# Sheet1.net
KiCad netlist of a schematic drawn in Altium Designer
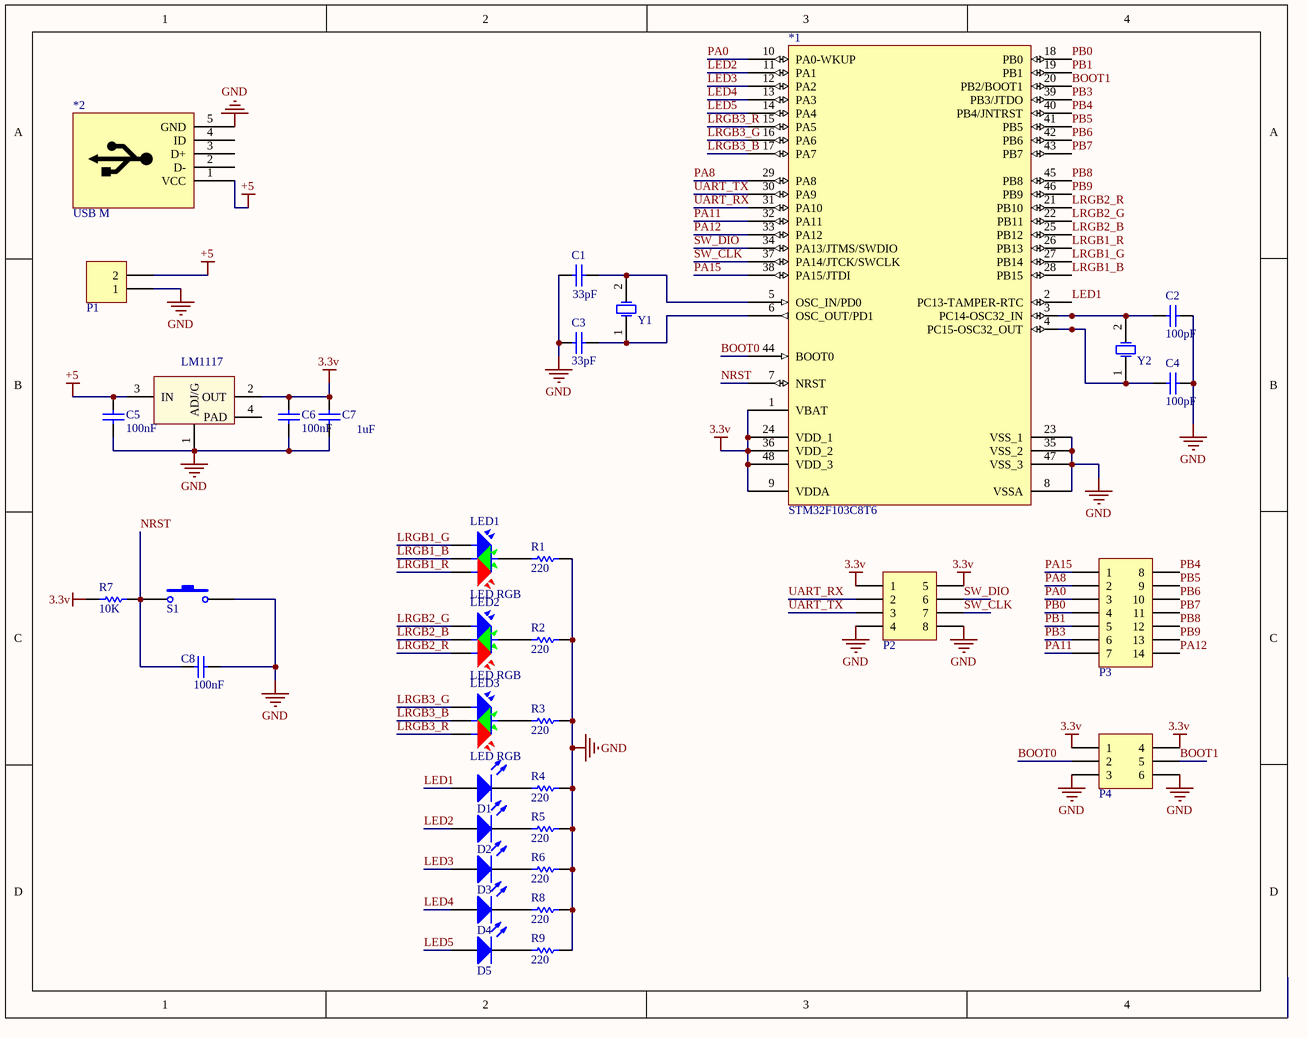
[diagram p0: Sheet1.SchDoc]

(export (version "E")
  (design (tool "Eeschema 10.0.6"))
  (components
    (comp (ref "*1")
      (value "STM32F103C8T6")
      (footprint "TSQFP50P900X900X160-48N")
      (fields (field (name "MANUFACTURER") "ST"))
      (libsource (lib "MiclsLib") (part "STM32F103C8T6"))
    )
    (comp (ref "*2")
      (value "USB M")
      (footprint "USB-B-MINI-SMD")
      (libsource (lib "My library altium") (part "USB M"))
    )
    (comp (ref "C1")
      (value "33pF")
      (footprint "CAP-SM-0805")
      (description "Capacitor")
      (fields (field (name "Comment") "Cap Non-Pol SMD"))
      (libsource (lib "PIF_Library") (part "Cap Non-Pol SMD"))
    )
    (comp (ref "C2")
      (value "100pF")
      (footprint "CAP-SM-0805")
      (description "Capacitor")
      (fields (field (name "Comment") "Cap Non-Pol SMD"))
      (libsource (lib "PIF_Library") (part "Cap Non-Pol SMD"))
    )
    (comp (ref "C3")
      (value "33pF")
      (footprint "CAP-SM-0805")
      (description "Capacitor")
      (fields (field (name "Comment") "Cap Non-Pol SMD"))
      (libsource (lib "PIF_Library") (part "Cap Non-Pol SMD"))
    )
    (comp (ref "C4")
      (value "100pF")
      (footprint "CAP-SM-0805")
      (description "Capacitor")
      (fields (field (name "Comment") "Cap Non-Pol SMD"))
      (libsource (lib "PIF_Library") (part "Cap Non-Pol SMD"))
    )
    (comp (ref "C5")
      (value "100nF")
      (footprint "CAP-SM-0805")
      (description "Capacitor")
      (fields (field (name "Comment") "Cap Non-Pol SMD"))
      (libsource (lib "PIF_Library") (part "Cap Non-Pol SMD"))
    )
    (comp (ref "C6")
      (value "100nF")
      (footprint "CAP-SM-0805")
      (description "Capacitor")
      (fields (field (name "Comment") "Cap Non-Pol SMD"))
      (libsource (lib "PIF_Library") (part "Cap Non-Pol SMD"))
    )
    (comp (ref "C7")
      (value "1uF")
      (footprint "CAP-SM-0805")
      (description "Capacitor")
      (fields (field (name "Comment") "Cap Non-Pol SMD"))
      (libsource (lib "PIF_Library") (part "Cap Non-Pol SMD"))
    )
    (comp (ref "C8")
      (value "100nF")
      (footprint "CAP-SM-0805")
      (description "Capacitor")
      (fields (field (name "Comment") "Cap Non-Pol SMD"))
      (libsource (lib "PIF_Library") (part "Cap Non-Pol SMD"))
    )
    (comp (ref "D1")
      (value "LED SMD")
      (footprint "LED_0603_Blue")
      (description "LED")
      (libsource (lib "PIF_Library") (part "LED SMD"))
    )
    (comp (ref "D2")
      (value "LED SMD")
      (footprint "LED_0603_Blue")
      (description "LED")
      (libsource (lib "PIF_Library") (part "LED SMD"))
    )
    (comp (ref "D3")
      (value "LED SMD")
      (footprint "LED_0603_Blue")
      (description "LED")
      (libsource (lib "PIF_Library") (part "LED SMD"))
    )
    (comp (ref "D4")
      (value "LED SMD")
      (footprint "LED_0603_Blue")
      (description "LED")
      (libsource (lib "PIF_Library") (part "LED SMD"))
    )
    (comp (ref "D5")
      (value "LED SMD")
      (footprint "LED_0603_Blue")
      (description "LED")
      (libsource (lib "PIF_Library") (part "LED SMD"))
    )
    (comp (ref "LED1")
      (value "LED RGB")
      (footprint "led rgb")
      (libsource (lib "My library altium") (part "LED RGB"))
    )
    (comp (ref "LED2")
      (value "LED RGB")
      (footprint "led rgb")
      (libsource (lib "My library altium") (part "LED RGB"))
    )
    (comp (ref "LED3")
      (value "LED RGB")
      (footprint "led rgb")
      (libsource (lib "My library altium") (part "LED RGB"))
    )
    (comp (ref "LM1117")
      (value "LM1117")
      (footprint "SOT223-4N")
      (description "Available in 1.8V, 2.5V, 2.85V, 3.3V, 5V, and  Adjustable Versions")
      (libsource (lib "PIF_Library") (part "LM1117"))
    )
    (comp (ref "P1")
      (value "Domino 2")
      (footprint "DOMINO 2- 5mm")
      (description "Domino, 2-Pin")
      (fields (field (name "PUBLISHER") "Altium Limited"))
      (libsource (lib "PIF_Library") (part "Domino 2"))
    )
    (comp (ref "P2")
      (value "Header 4X2")
      (footprint "JP4x2")
      (description "Header, 4-Pin, Dual row")
      (fields (field (name "PUBLISHER") "Altium Limited"))
      (libsource (lib "PIF_Library") (part "Header 4X2"))
    )
    (comp (ref "P3")
      (value "Header 7X2")
      (footprint "JP7X2")
      (description "Header, 7-Pin, Dual row")
      (fields (field (name "PUBLISHER") "Altium Limited"))
      (libsource (lib "PIF_Library") (part "Header 7X2"))
    )
    (comp (ref "P4")
      (value "Header 3X2")
      (footprint "JP3x2")
      (description "Header, 3-Pin, Dual row")
      (fields (field (name "PUBLISHER") "Altium Limited"))
      (libsource (lib "PIF_Library") (part "Header 3X2"))
    )
    (comp (ref "R1")
      (value "220")
      (footprint "RES-SM-0603")
      (description "Resistor")
      (fields (field (name "Comment") "RESISTOR SMD"))
      (libsource (lib "PIF_Library") (part "RESISTOR SMD"))
    )
    (comp (ref "R2")
      (value "220")
      (footprint "RES-SM-0603")
      (description "Resistor")
      (fields (field (name "Comment") "RESISTOR SMD"))
      (libsource (lib "PIF_Library") (part "RESISTOR SMD"))
    )
    (comp (ref "R3")
      (value "220")
      (footprint "RES-SM-0603")
      (description "Resistor")
      (fields (field (name "Comment") "RESISTOR SMD"))
      (libsource (lib "PIF_Library") (part "RESISTOR SMD"))
    )
    (comp (ref "R4")
      (value "220")
      (footprint "RES-SM-0603")
      (description "Resistor")
      (fields (field (name "Comment") "RESISTOR SMD"))
      (libsource (lib "PIF_Library") (part "RESISTOR SMD"))
    )
    (comp (ref "R5")
      (value "220")
      (footprint "RES-SM-0603")
      (description "Resistor")
      (fields (field (name "Comment") "RESISTOR SMD"))
      (libsource (lib "PIF_Library") (part "RESISTOR SMD"))
    )
    (comp (ref "R6")
      (value "220")
      (footprint "RES-SM-0603")
      (description "Resistor")
      (fields (field (name "Comment") "RESISTOR SMD"))
      (libsource (lib "PIF_Library") (part "RESISTOR SMD"))
    )
    (comp (ref "R7")
      (value "10K")
      (footprint "RES-SM-0603")
      (description "Resistor")
      (fields (field (name "Comment") "RESISTOR SMD"))
      (libsource (lib "PIF_Library") (part "RESISTOR SMD"))
    )
    (comp (ref "R8")
      (value "220")
      (footprint "RES-SM-0603")
      (description "Resistor")
      (fields (field (name "Comment") "RESISTOR SMD"))
      (libsource (lib "PIF_Library") (part "RESISTOR SMD"))
    )
    (comp (ref "R9")
      (value "220")
      (footprint "RES-SM-0603")
      (description "Resistor")
      (fields (field (name "Comment") "RESISTOR SMD"))
      (libsource (lib "PIF_Library") (part "RESISTOR SMD"))
    )
    (comp (ref "S1")
      (value "Tact SW - 2Pin")
      (footprint "SW2")
      (description "Switch button 2 pin")
      (libsource (lib "PIF_Library") (part "Tact SW - 2Pin"))
    )
    (comp (ref "Y1")
      (value "XTAL")
      (footprint "XTAL 32KN")
      (description "Crystal Oscillator")
      (fields (field (name "PUBLISHER") "Altium Limited"))
      (libsource (lib "PIF_Library") (part "XTAL"))
    )
    (comp (ref "Y2")
      (value "XTAL")
      (footprint "XTAL 32KN")
      (description "Crystal Oscillator")
      (fields (field (name "PUBLISHER") "Altium Limited"))
      (libsource (lib "PIF_Library") (part "XTAL"))
    )
  )
  (nets
    (net (code "1") (name "+5") (class "Default")
      (node (ref "*2") (pin "1") (pinfunction "VCC_1") (pintype "passive"))
      (node (ref "C5") (pin "1") (pinfunction "1_1") (pintype "passive"))
      (node (ref "LM1117") (pin "3") (pinfunction "IN_3") (pintype "passive"))
      (node (ref "P1") (pin "2") (pinfunction "2_2") (pintype "passive"))
    )
    (net (code "2") (name "/BOOT0") (class "Default")
      (node (ref "*1") (pin "44") (pinfunction "BOOT0_44") (pintype "input"))
      (node (ref "P4") (pin "2") (pinfunction "2_2") (pintype "passive"))
    )
    (net (code "3") (name "/BOOT1") (class "Default")
      (node (ref "*1") (pin "20") (pinfunction "PB2/BOOT1_20") (pintype "bidirectional"))
      (node (ref "P4") (pin "5") (pinfunction "5_5") (pintype "passive"))
    )
    (net (code "4") (name "/LED1") (class "Default")
      (node (ref "*1") (pin "2") (pinfunction "PC13-TAMPER-RTC_2") (pintype "bidirectional"))
      (node (ref "D1") (pin "1") (pinfunction "A_1") (pintype "passive"))
    )
    (net (code "5") (name "/LED2") (class "Default")
      (node (ref "*1") (pin "11") (pinfunction "PA1_11") (pintype "bidirectional"))
      (node (ref "D2") (pin "1") (pinfunction "A_1") (pintype "passive"))
    )
    (net (code "6") (name "/LED3") (class "Default")
      (node (ref "*1") (pin "12") (pinfunction "PA2_12") (pintype "bidirectional"))
      (node (ref "D3") (pin "1") (pinfunction "A_1") (pintype "passive"))
    )
    (net (code "7") (name "/LED4") (class "Default")
      (node (ref "*1") (pin "13") (pinfunction "PA3_13") (pintype "bidirectional"))
      (node (ref "D4") (pin "1") (pinfunction "A_1") (pintype "passive"))
    )
    (net (code "8") (name "/LED5") (class "Default")
      (node (ref "*1") (pin "14") (pinfunction "PA4_14") (pintype "bidirectional"))
      (node (ref "D5") (pin "1") (pinfunction "A_1") (pintype "passive"))
    )
    (net (code "9") (name "/LRGB1_B") (class "Default")
      (node (ref "*1") (pin "28") (pinfunction "PB15_28") (pintype "bidirectional"))
      (node (ref "LED1") (pin "1") (pinfunction "1_1") (pintype "passive"))
    )
    (net (code "10") (name "/LRGB1_G") (class "Default")
      (node (ref "*1") (pin "27") (pinfunction "PB14_27") (pintype "bidirectional"))
      (node (ref "LED1") (pin "2") (pinfunction "2_2") (pintype "passive"))
    )
    (net (code "11") (name "/LRGB1_R") (class "Default")
      (node (ref "*1") (pin "26") (pinfunction "PB13_26") (pintype "bidirectional"))
      (node (ref "LED1") (pin "4") (pinfunction "4_4") (pintype "passive"))
    )
    (net (code "12") (name "/LRGB2_B") (class "Default")
      (node (ref "*1") (pin "25") (pinfunction "PB12_25") (pintype "bidirectional"))
      (node (ref "LED2") (pin "1") (pinfunction "1_1") (pintype "passive"))
    )
    (net (code "13") (name "/LRGB2_G") (class "Default")
      (node (ref "*1") (pin "22") (pinfunction "PB11_22") (pintype "bidirectional"))
      (node (ref "LED2") (pin "2") (pinfunction "2_2") (pintype "passive"))
    )
    (net (code "14") (name "/LRGB2_R") (class "Default")
      (node (ref "*1") (pin "21") (pinfunction "PB10_21") (pintype "bidirectional"))
      (node (ref "LED2") (pin "4") (pinfunction "4_4") (pintype "passive"))
    )
    (net (code "15") (name "/LRGB3_B") (class "Default")
      (node (ref "*1") (pin "17") (pinfunction "PA7_17") (pintype "bidirectional"))
      (node (ref "LED3") (pin "1") (pinfunction "1_1") (pintype "passive"))
    )
    (net (code "16") (name "/LRGB3_G") (class "Default")
      (node (ref "*1") (pin "16") (pinfunction "PA6_16") (pintype "bidirectional"))
      (node (ref "LED3") (pin "2") (pinfunction "2_2") (pintype "passive"))
    )
    (net (code "17") (name "/LRGB3_R") (class "Default")
      (node (ref "*1") (pin "15") (pinfunction "PA5_15") (pintype "bidirectional"))
      (node (ref "LED3") (pin "4") (pinfunction "4_4") (pintype "passive"))
    )
    (net (code "18") (name "/NRST") (class "Default")
      (node (ref "*1") (pin "7") (pinfunction "NRST_7") (pintype "bidirectional"))
      (node (ref "C8") (pin "1") (pinfunction "1_1") (pintype "passive"))
      (node (ref "R7") (pin "2") (pinfunction "2_2") (pintype "passive"))
      (node (ref "S1") (pin "1") (pinfunction "1_1") (pintype "passive"))
    )
    (net (code "19") (name "/PA0") (class "Default")
      (node (ref "*1") (pin "10") (pinfunction "PA0-WKUP_10") (pintype "bidirectional"))
      (node (ref "P3") (pin "3") (pinfunction "3_3") (pintype "passive"))
    )
    (net (code "20") (name "/PA8") (class "Default")
      (node (ref "*1") (pin "29") (pinfunction "PA8_29") (pintype "bidirectional"))
      (node (ref "P3") (pin "2") (pinfunction "2_2") (pintype "passive"))
    )
    (net (code "21") (name "/PA11") (class "Default")
      (node (ref "*1") (pin "32") (pinfunction "PA11_32") (pintype "bidirectional"))
      (node (ref "P3") (pin "7") (pinfunction "7_7") (pintype "passive"))
    )
    (net (code "22") (name "/PA12") (class "Default")
      (node (ref "*1") (pin "33") (pinfunction "PA12_33") (pintype "bidirectional"))
      (node (ref "P3") (pin "14") (pinfunction "14_14") (pintype "passive"))
    )
    (net (code "23") (name "/PA15") (class "Default")
      (node (ref "*1") (pin "38") (pinfunction "PA15/JTDI_38") (pintype "bidirectional"))
      (node (ref "P3") (pin "1") (pinfunction "1_1") (pintype "passive"))
    )
    (net (code "24") (name "/PB0") (class "Default")
      (node (ref "*1") (pin "18") (pinfunction "PB0_18") (pintype "bidirectional"))
      (node (ref "P3") (pin "4") (pinfunction "4_4") (pintype "passive"))
    )
    (net (code "25") (name "/PB1") (class "Default")
      (node (ref "*1") (pin "19") (pinfunction "PB1_19") (pintype "bidirectional"))
      (node (ref "P3") (pin "5") (pinfunction "5_5") (pintype "passive"))
    )
    (net (code "26") (name "/PB3") (class "Default")
      (node (ref "*1") (pin "39") (pinfunction "PB3/JTDO_39") (pintype "bidirectional"))
      (node (ref "P3") (pin "6") (pinfunction "6_6") (pintype "passive"))
    )
    (net (code "27") (name "/PB4") (class "Default")
      (node (ref "*1") (pin "40") (pinfunction "PB4/JNTRST_40") (pintype "bidirectional"))
      (node (ref "P3") (pin "8") (pinfunction "8_8") (pintype "passive"))
    )
    (net (code "28") (name "/PB5") (class "Default")
      (node (ref "*1") (pin "41") (pinfunction "PB5_41") (pintype "bidirectional"))
      (node (ref "P3") (pin "9") (pinfunction "9_9") (pintype "passive"))
    )
    (net (code "29") (name "/PB6") (class "Default")
      (node (ref "*1") (pin "42") (pinfunction "PB6_42") (pintype "bidirectional"))
      (node (ref "P3") (pin "10") (pinfunction "10_10") (pintype "passive"))
    )
    (net (code "30") (name "/PB7") (class "Default")
      (node (ref "*1") (pin "43") (pinfunction "PB7_43") (pintype "bidirectional"))
      (node (ref "P3") (pin "11") (pinfunction "11_11") (pintype "passive"))
    )
    (net (code "31") (name "/PB8") (class "Default")
      (node (ref "*1") (pin "45") (pinfunction "PB8_45") (pintype "bidirectional"))
      (node (ref "P3") (pin "12") (pinfunction "12_12") (pintype "passive"))
    )
    (net (code "32") (name "/PB9") (class "Default")
      (node (ref "*1") (pin "46") (pinfunction "PB9_46") (pintype "bidirectional"))
      (node (ref "P3") (pin "13") (pinfunction "13_13") (pintype "passive"))
    )
    (net (code "33") (name "/SW_CLK") (class "Default")
      (node (ref "*1") (pin "37") (pinfunction "PA14/JTCK/SWCLK_37") (pintype "bidirectional"))
      (node (ref "P2") (pin "7") (pinfunction "7_7") (pintype "passive"))
    )
    (net (code "34") (name "/SW_DIO") (class "Default")
      (node (ref "*1") (pin "34") (pinfunction "PA13/JTMS/SWDIO_34") (pintype "bidirectional"))
      (node (ref "P2") (pin "6") (pinfunction "6_6") (pintype "passive"))
    )
    (net (code "35") (name "/UART_RX") (class "Default")
      (node (ref "*1") (pin "31") (pinfunction "PA10_31") (pintype "bidirectional"))
      (node (ref "P2") (pin "2") (pinfunction "2_2") (pintype "passive"))
    )
    (net (code "36") (name "/UART_TX") (class "Default")
      (node (ref "*1") (pin "30") (pinfunction "PA9_30") (pintype "bidirectional"))
      (node (ref "P2") (pin "3") (pinfunction "3_3") (pintype "passive"))
    )
    (net (code "37") (name "3.3v") (class "Default")
      (node (ref "*1") (pin "1") (pinfunction "VBAT_1") (pintype "power_in"))
      (node (ref "*1") (pin "24") (pinfunction "VDD_1_24") (pintype "power_in"))
      (node (ref "*1") (pin "36") (pinfunction "VDD_2_36") (pintype "power_in"))
      (node (ref "*1") (pin "48") (pinfunction "VDD_3_48") (pintype "power_in"))
      (node (ref "*1") (pin "9") (pinfunction "VDDA_9") (pintype "power_in"))
      (node (ref "C6") (pin "1") (pinfunction "1_1") (pintype "passive"))
      (node (ref "C7") (pin "1") (pinfunction "1_1") (pintype "passive"))
      (node (ref "LM1117") (pin "2") (pinfunction "OUT_2") (pintype "passive"))
      (node (ref "P2") (pin "1") (pinfunction "1_1") (pintype "passive"))
      (node (ref "P2") (pin "5") (pinfunction "5_5") (pintype "passive"))
      (node (ref "P4") (pin "1") (pinfunction "1_1") (pintype "passive"))
      (node (ref "P4") (pin "4") (pinfunction "4_4") (pintype "passive"))
      (node (ref "R7") (pin "1") (pinfunction "1_1") (pintype "passive"))
    )
    (net (code "38") (name "GND") (class "Default")
      (node (ref "*1") (pin "23") (pinfunction "VSS_1_23") (pintype "power_in"))
      (node (ref "*1") (pin "35") (pinfunction "VSS_2_35") (pintype "power_in"))
      (node (ref "*1") (pin "47") (pinfunction "VSS_3_47") (pintype "power_in"))
      (node (ref "*1") (pin "8") (pinfunction "VSSA_8") (pintype "power_in"))
      (node (ref "*2") (pin "5") (pinfunction "GND_5") (pintype "passive"))
      (node (ref "C1") (pin "1") (pinfunction "1_1") (pintype "passive"))
      (node (ref "C2") (pin "2") (pinfunction "2_2") (pintype "passive"))
      (node (ref "C3") (pin "1") (pinfunction "1_1") (pintype "passive"))
      (node (ref "C4") (pin "2") (pinfunction "2_2") (pintype "passive"))
      (node (ref "C5") (pin "2") (pinfunction "2_2") (pintype "passive"))
      (node (ref "C6") (pin "2") (pinfunction "2_2") (pintype "passive"))
      (node (ref "C7") (pin "2") (pinfunction "2_2") (pintype "passive"))
      (node (ref "C8") (pin "2") (pinfunction "2_2") (pintype "passive"))
      (node (ref "LM1117") (pin "1") (pinfunction "ADJ/G_1") (pintype "passive"))
      (node (ref "P1") (pin "1") (pinfunction "1_1") (pintype "passive"))
      (node (ref "P2") (pin "4") (pinfunction "4_4") (pintype "passive"))
      (node (ref "P2") (pin "8") (pinfunction "8_8") (pintype "passive"))
      (node (ref "P4") (pin "3") (pinfunction "3_3") (pintype "passive"))
      (node (ref "P4") (pin "6") (pinfunction "6_6") (pintype "passive"))
      (node (ref "R1") (pin "1") (pinfunction "1_1") (pintype "passive"))
      (node (ref "R2") (pin "1") (pinfunction "1_1") (pintype "passive"))
      (node (ref "R3") (pin "1") (pinfunction "1_1") (pintype "passive"))
      (node (ref "R4") (pin "1") (pinfunction "1_1") (pintype "passive"))
      (node (ref "R5") (pin "1") (pinfunction "1_1") (pintype "passive"))
      (node (ref "R6") (pin "1") (pinfunction "1_1") (pintype "passive"))
      (node (ref "R8") (pin "1") (pinfunction "1_1") (pintype "passive"))
      (node (ref "R9") (pin "1") (pinfunction "1_1") (pintype "passive"))
      (node (ref "S1") (pin "2") (pinfunction "2_2") (pintype "passive"))
    )
    (net (code "39") (name "Net-(*1-OSC_IN{slash}PD0)") (class "Default")
      (node (ref "*1") (pin "5") (pinfunction "OSC_IN/PD0_5") (pintype "input"))
      (node (ref "C1") (pin "2") (pinfunction "2_2") (pintype "passive"))
      (node (ref "Y1") (pin "2") (pinfunction "OSC2_2") (pintype "passive"))
    )
    (net (code "40") (name "Net-(*1-OSC_OUT{slash}PD1)") (class "Default")
      (node (ref "*1") (pin "6") (pinfunction "OSC_OUT/PD1_6") (pintype "output"))
      (node (ref "C3") (pin "2") (pinfunction "2_2") (pintype "passive"))
      (node (ref "Y1") (pin "1") (pinfunction "OSC1_1") (pintype "passive"))
    )
    (net (code "41") (name "Net-(*1-PC14-OSC32_IN)") (class "Default")
      (node (ref "*1") (pin "3") (pinfunction "PC14-OSC32_IN_3") (pintype "bidirectional"))
      (node (ref "C2") (pin "1") (pinfunction "1_1") (pintype "passive"))
      (node (ref "Y2") (pin "2") (pinfunction "OSC2_2") (pintype "passive"))
    )
    (net (code "42") (name "Net-(*1-PC15-OSC32_OUT)") (class "Default")
      (node (ref "*1") (pin "4") (pinfunction "PC15-OSC32_OUT_4") (pintype "bidirectional"))
      (node (ref "C4") (pin "1") (pinfunction "1_1") (pintype "passive"))
      (node (ref "Y2") (pin "1") (pinfunction "OSC1_1") (pintype "passive"))
    )
    (net (code "43") (name "Net-(D1-K)") (class "Default")
      (node (ref "D1") (pin "2") (pinfunction "K_2") (pintype "passive"))
      (node (ref "R4") (pin "2") (pinfunction "2_2") (pintype "passive"))
    )
    (net (code "44") (name "Net-(D2-K)") (class "Default")
      (node (ref "D2") (pin "2") (pinfunction "K_2") (pintype "passive"))
      (node (ref "R5") (pin "2") (pinfunction "2_2") (pintype "passive"))
    )
    (net (code "45") (name "Net-(D3-K)") (class "Default")
      (node (ref "D3") (pin "2") (pinfunction "K_2") (pintype "passive"))
      (node (ref "R6") (pin "2") (pinfunction "2_2") (pintype "passive"))
    )
    (net (code "46") (name "Net-(D4-K)") (class "Default")
      (node (ref "D4") (pin "2") (pinfunction "K_2") (pintype "passive"))
      (node (ref "R8") (pin "2") (pinfunction "2_2") (pintype "passive"))
    )
    (net (code "47") (name "Net-(D5-K)") (class "Default")
      (node (ref "D5") (pin "2") (pinfunction "K_2") (pintype "passive"))
      (node (ref "R9") (pin "2") (pinfunction "2_2") (pintype "passive"))
    )
    (net (code "48") (name "Net-(LED1-Pad3)") (class "Default")
      (node (ref "LED1") (pin "3") (pinfunction "3_3") (pintype "passive"))
      (node (ref "R1") (pin "2") (pinfunction "2_2") (pintype "passive"))
    )
    (net (code "49") (name "Net-(LED2-Pad3)") (class "Default")
      (node (ref "LED2") (pin "3") (pinfunction "3_3") (pintype "passive"))
      (node (ref "R2") (pin "2") (pinfunction "2_2") (pintype "passive"))
    )
    (net (code "50") (name "Net-(LED3-Pad3)") (class "Default")
      (node (ref "LED3") (pin "3") (pinfunction "3_3") (pintype "passive"))
      (node (ref "R3") (pin "2") (pinfunction "2_2") (pintype "passive"))
    )
    (net (code "51") (name "unconnected-(*2-D+-Pad3)") (class "Default")
      (node (ref "*2") (pin "3") (pinfunction "D+_3") (pintype "passive"))
    )
    (net (code "52") (name "unconnected-(*2-D--Pad2)") (class "Default")
      (node (ref "*2") (pin "2") (pinfunction "D-_2") (pintype "passive"))
    )
    (net (code "53") (name "unconnected-(*2-ID-Pad4)") (class "Default")
      (node (ref "*2") (pin "4") (pinfunction "ID_4") (pintype "passive"))
    )
    (net (code "54") (name "unconnected-(LM1117-PAD-Pad4)") (class "Default")
      (node (ref "LM1117") (pin "4") (pinfunction "PAD_4") (pintype "passive"))
    )
  )
)
